# v12.net
KiCad netlist of a schematic drawn in EAGLE
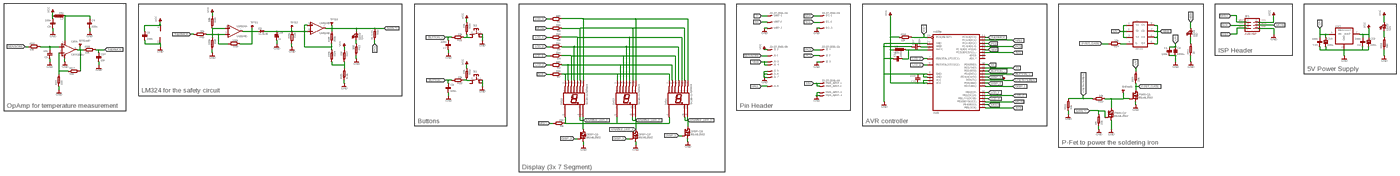
[diagram p0: schematic, sheet 1, overview]
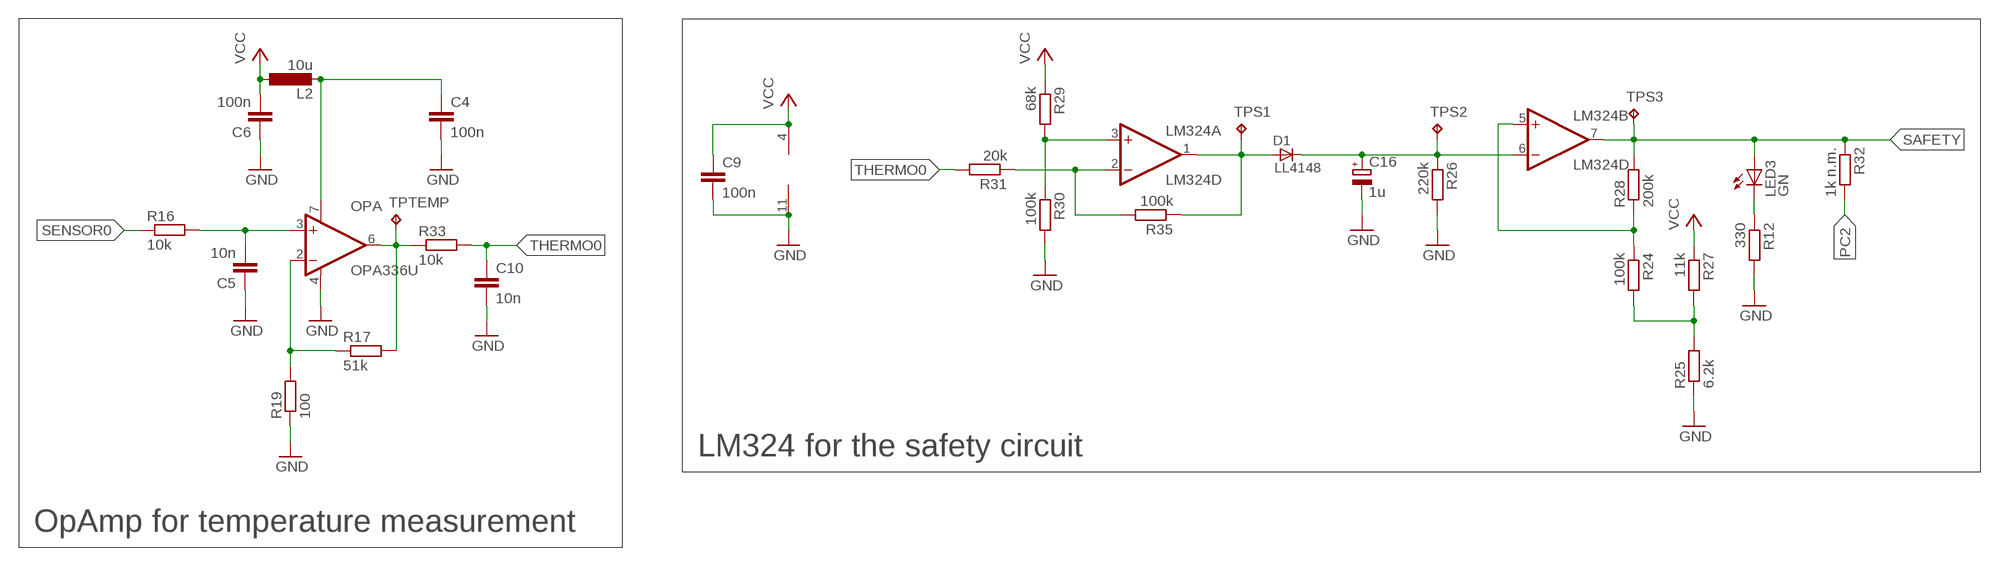
[diagram p1: schematic, sheet 1, part 1 of 4]
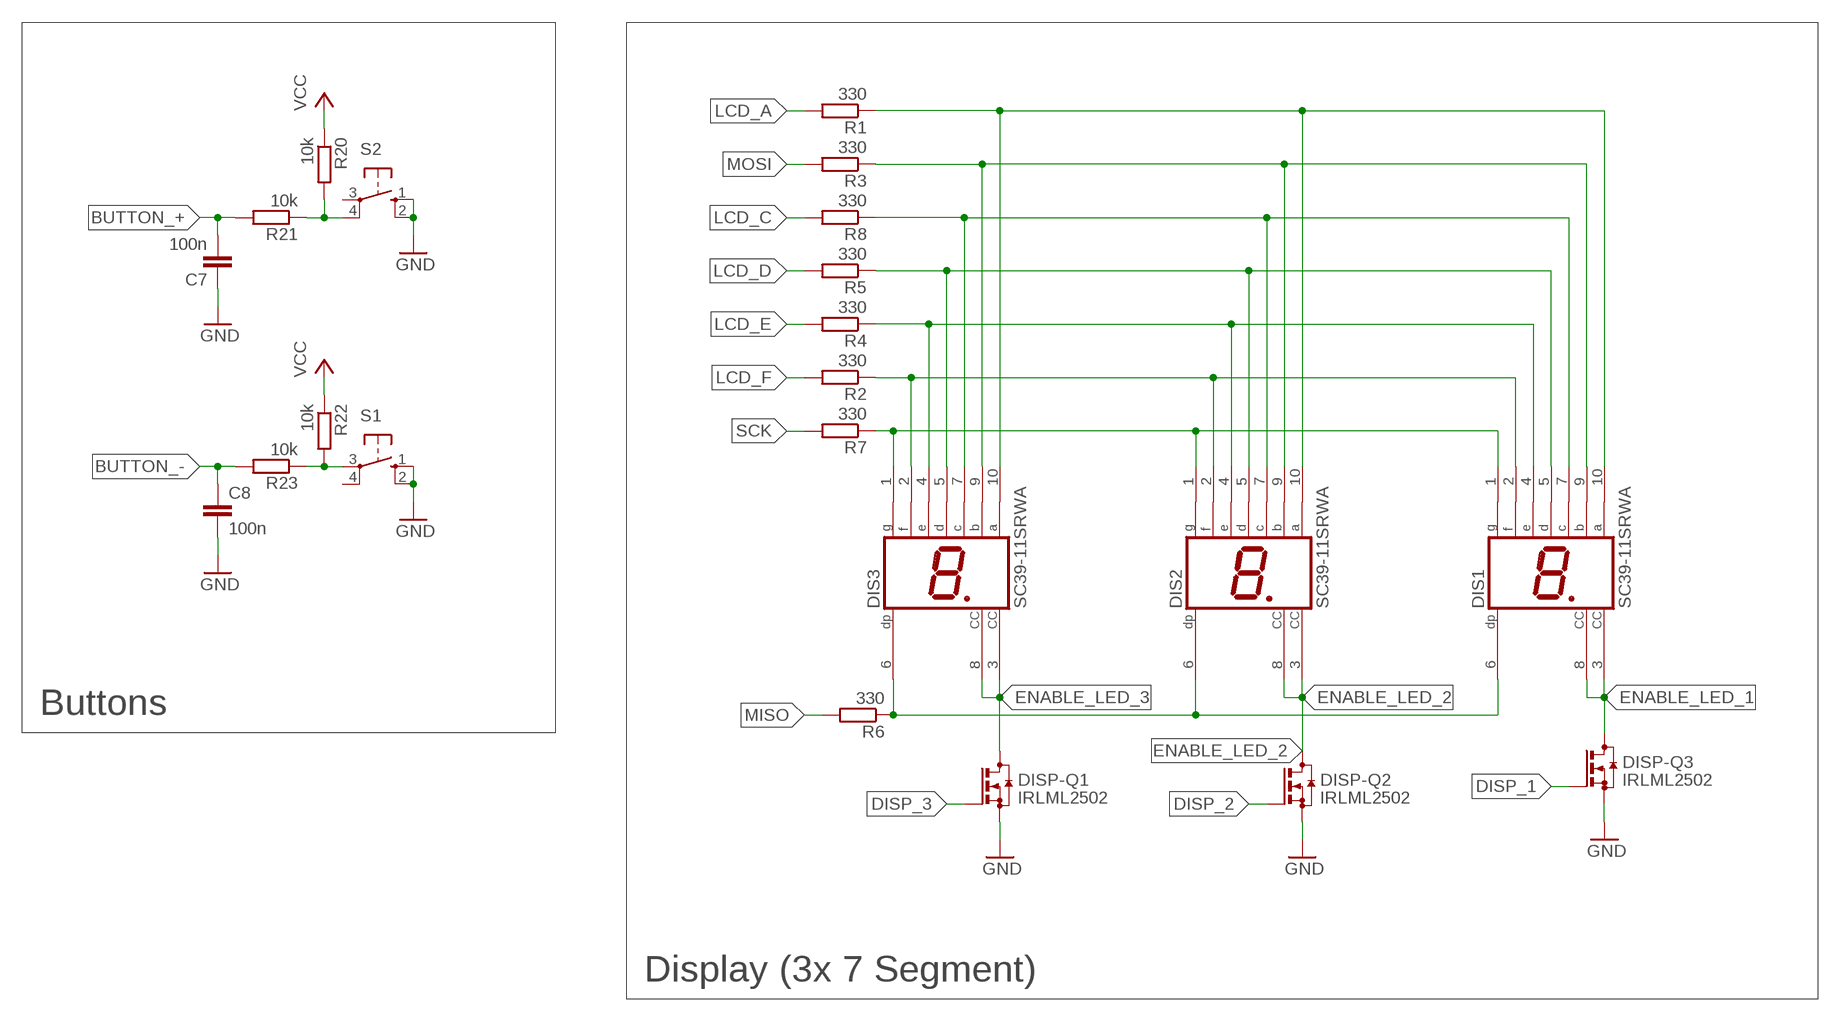
[diagram p2: schematic, sheet 1, part 2 of 4]
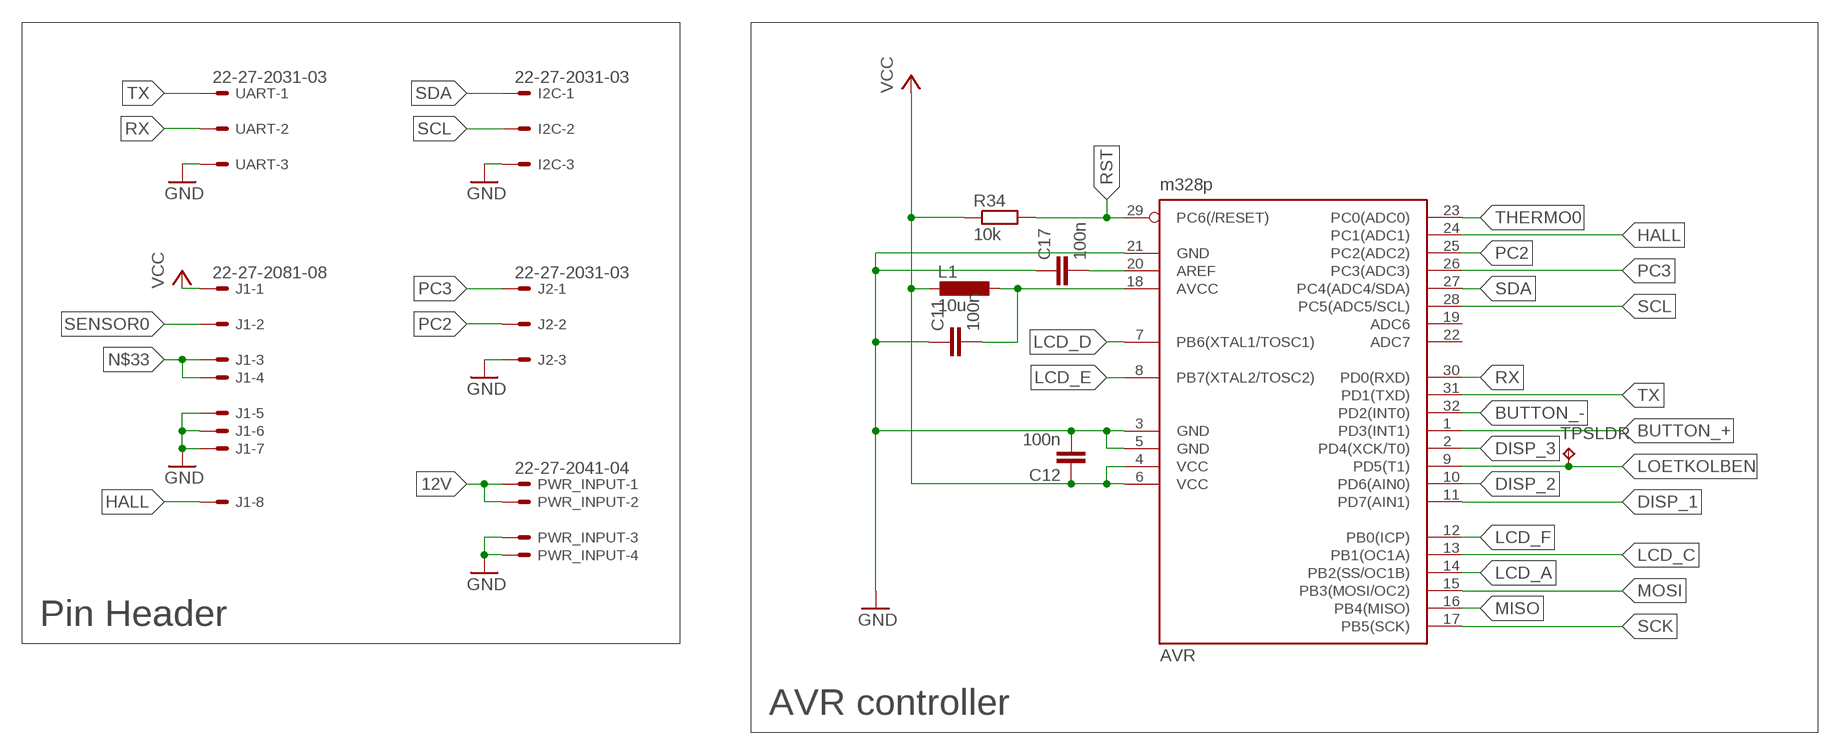
[diagram p3: schematic, sheet 1, part 3 of 4]
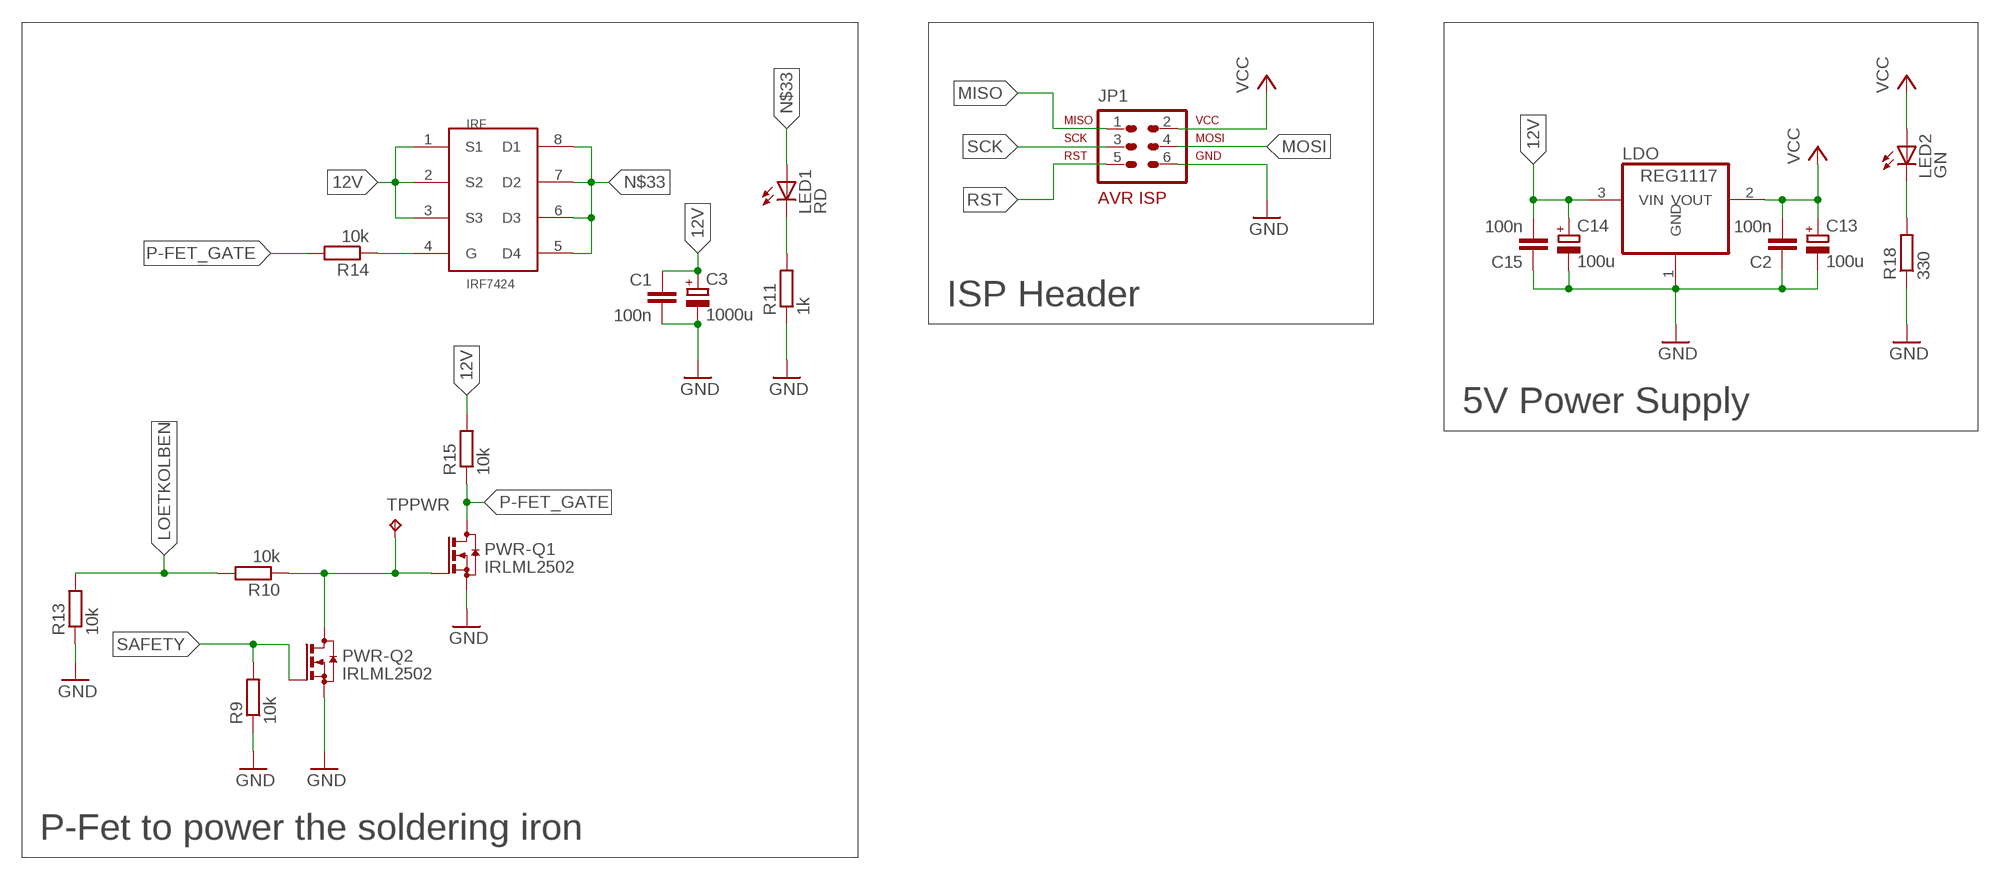
[diagram p4: schematic, sheet 1, part 4 of 4]

(export (version "E")
  (design (tool "Eeschema 10.0.6"))
  (components
    (comp (ref "AVR")
      (value "m328p")
      (footprint "eagle-import:TQFP32-08")
      (fields (field (name "MPN") "ATMEGA8-16AU"))
      (libsource (lib "eagle-import") (part "MEGA8-AI"))
    )
    (comp (ref "C1")
      (value "100n")
      (footprint "eagle-import:C0603")
      (libsource (lib "eagle-import") (part "C-EUC0603"))
    )
    (comp (ref "C2")
      (value "100n")
      (footprint "eagle-import:C0603")
      (libsource (lib "eagle-import") (part "C-EUC0603"))
    )
    (comp (ref "C3")
      (value "1000u")
      (footprint "eagle-import:E5-13")
      (libsource (lib "eagle-import") (part "CPOL-EUE5-13"))
    )
    (comp (ref "C4")
      (value "100n")
      (footprint "eagle-import:C0603")
      (libsource (lib "eagle-import") (part "C-EUC0603"))
    )
    (comp (ref "C5")
      (value "10n")
      (footprint "eagle-import:C0603")
      (libsource (lib "eagle-import") (part "C-EUC0603"))
    )
    (comp (ref "C6")
      (value "100n")
      (footprint "eagle-import:C0603")
      (libsource (lib "eagle-import") (part "C-EUC0603"))
    )
    (comp (ref "C7")
      (value "100n")
      (footprint "eagle-import:C0603")
      (libsource (lib "eagle-import") (part "C-EUC0603"))
    )
    (comp (ref "C8")
      (value "100n")
      (footprint "eagle-import:C0603")
      (libsource (lib "eagle-import") (part "C-EUC0603"))
    )
    (comp (ref "C9")
      (value "100n")
      (footprint "eagle-import:C0603")
      (libsource (lib "eagle-import") (part "C-EUC0603"))
    )
    (comp (ref "C10")
      (value "10n")
      (footprint "eagle-import:C0603")
      (libsource (lib "eagle-import") (part "C-EUC0603"))
    )
    (comp (ref "C11")
      (value "100n")
      (footprint "eagle-import:C0603")
      (libsource (lib "eagle-import") (part "C-EUC0603"))
    )
    (comp (ref "C12")
      (value "100n")
      (footprint "eagle-import:C0603")
      (libsource (lib "eagle-import") (part "C-EUC0603"))
    )
    (comp (ref "C13")
      (value "100u")
      (footprint "eagle-import:E2-5")
      (libsource (lib "eagle-import") (part "CPOL-EUE2-5"))
    )
    (comp (ref "C14")
      (value "100u")
      (footprint "eagle-import:E2-5")
      (libsource (lib "eagle-import") (part "CPOL-EUE2-5"))
    )
    (comp (ref "C15")
      (value "100n")
      (footprint "eagle-import:C0603")
      (libsource (lib "eagle-import") (part "C-EUC0603"))
    )
    (comp (ref "C16")
      (value "1u")
      (footprint "eagle-import:E2-5")
      (libsource (lib "eagle-import") (part "CPOL-EUE2-5"))
    )
    (comp (ref "C17")
      (value "100n")
      (footprint "eagle-import:C0603")
      (libsource (lib "eagle-import") (part "C-EUC0603"))
    )
    (comp (ref "D1")
      (value "LL4148")
      (footprint "eagle-import:SOD80_DO213AA_MINIMELF")
      (libsource (lib "eagle-import") (part "LL4148"))
    )
    (comp (ref "DIS1")
      (value "SC39-11SRWA")
      (footprint "eagle-import:HDSP-E")
      (libsource (lib "eagle-import") (part "SC39-11SRWA"))
    )
    (comp (ref "DIS2")
      (value "SC39-11SRWA")
      (footprint "eagle-import:HDSP-E")
      (libsource (lib "eagle-import") (part "SC39-11SRWA"))
    )
    (comp (ref "DIS3")
      (value "SC39-11SRWA")
      (footprint "eagle-import:HDSP-E")
      (libsource (lib "eagle-import") (part "SC39-11SRWA"))
    )
    (comp (ref "DISP-Q1")
      (value "IRLML2502")
      (footprint "eagle-import:SOT23")
      (libsource (lib "eagle-import") (part "BSS123"))
    )
    (comp (ref "DISP-Q2")
      (value "IRLML2502")
      (footprint "eagle-import:SOT23")
      (libsource (lib "eagle-import") (part "BSS123"))
    )
    (comp (ref "DISP-Q3")
      (value "IRLML2502")
      (footprint "eagle-import:SOT23")
      (libsource (lib "eagle-import") (part "BSS123"))
    )
    (comp (ref "I2C")
      (value "22-27-2031-03")
      (footprint "eagle-import:6410-03")
      (libsource (lib "eagle-import") (part "22-?-0327-2031"))
    )
    (comp (ref "IRF")
      (value "IRF7424")
      (footprint "eagle-import:SO-08")
      (libsource (lib "eagle-import") (part "IRF7424"))
    )
    (comp (ref "J1")
      (value "22-27-2081-08")
      (footprint "eagle-import:6410-08")
      (libsource (lib "eagle-import") (part "22-?-0827-2081"))
    )
    (comp (ref "J2")
      (value "22-27-2031-03")
      (footprint "eagle-import:6410-03")
      (libsource (lib "eagle-import") (part "22-?-0327-2031"))
    )
    (comp (ref "JP1")
      (value "AVR-ISP-6VERT")
      (footprint "eagle-import:AVR-ISP-6")
      (libsource (lib "eagle-import") (part "AVR-ISP-6VERT"))
    )
    (comp (ref "L1")
      (value "10u")
      (footprint "eagle-import:L2825P")
      (libsource (lib "eagle-import") (part "L-EUL2825P"))
    )
    (comp (ref "L2")
      (value "10u")
      (footprint "eagle-import:L2825P")
      (libsource (lib "eagle-import") (part "L-EUL2825P"))
    )
    (comp (ref "LDO")
      (value "REG1117")
      (footprint "eagle-import:SOT223")
      (libsource (lib "eagle-import") (part "REG1117"))
    )
    (comp (ref "LED1")
      (value "RD")
      (footprint "eagle-import:CHIP-LED0805")
      (libsource (lib "eagle-import") (part "LEDCHIP-LED0805"))
    )
    (comp (ref "LED2")
      (value "GN")
      (footprint "eagle-import:CHIP-LED0805")
      (libsource (lib "eagle-import") (part "LEDCHIP-LED0805"))
    )
    (comp (ref "LED3")
      (value "GN")
      (footprint "eagle-import:CHIP-LED0805")
      (libsource (lib "eagle-import") (part "LEDCHIP-LED0805"))
    )
    (comp (ref "LM324")
      (value "LM324D")
      (footprint "eagle-import:SO14")
      (libsource (lib "eagle-import") (part "LM324D"))
    )
    (comp (ref "OPA")
      (value "OPA336U")
      (footprint "eagle-import:SO08")
      (fields (field (name "MF") "TEXAS INSTRUMENT CONNECTORS") (field (name "MPN") "OPA336UA"))
      (libsource (lib "eagle-import") (part "OPA336U"))
    )
    (comp (ref "PWR-Q1")
      (value "IRLML2502")
      (footprint "eagle-import:SOT23")
      (libsource (lib "eagle-import") (part "BSS123"))
    )
    (comp (ref "PWR-Q2")
      (value "IRLML2502")
      (footprint "eagle-import:SOT23")
      (libsource (lib "eagle-import") (part "BSS123"))
    )
    (comp (ref "PWR_INPUT")
      (value "22-27-2041-04")
      (footprint "eagle-import:6410-04")
      (libsource (lib "eagle-import") (part "22-?-0427-2041"))
    )
    (comp (ref "R1")
      (value "330")
      (footprint "eagle-import:R0603")
      (libsource (lib "eagle-import") (part "R-EU_R0603"))
    )
    (comp (ref "R2")
      (value "330")
      (footprint "eagle-import:R0603")
      (libsource (lib "eagle-import") (part "R-EU_R0603"))
    )
    (comp (ref "R3")
      (value "330")
      (footprint "eagle-import:R0603")
      (libsource (lib "eagle-import") (part "R-EU_R0603"))
    )
    (comp (ref "R4")
      (value "330")
      (footprint "eagle-import:R0603")
      (libsource (lib "eagle-import") (part "R-EU_R0603"))
    )
    (comp (ref "R5")
      (value "330")
      (footprint "eagle-import:R0603")
      (libsource (lib "eagle-import") (part "R-EU_R0603"))
    )
    (comp (ref "R6")
      (value "330")
      (footprint "eagle-import:R0603")
      (libsource (lib "eagle-import") (part "R-EU_R0603"))
    )
    (comp (ref "R7")
      (value "330")
      (footprint "eagle-import:R0603")
      (libsource (lib "eagle-import") (part "R-EU_R0603"))
    )
    (comp (ref "R8")
      (value "330")
      (footprint "eagle-import:R0603")
      (libsource (lib "eagle-import") (part "R-EU_R0603"))
    )
    (comp (ref "R9")
      (value "10k")
      (footprint "eagle-import:R0603")
      (libsource (lib "eagle-import") (part "R-EU_R0603"))
    )
    (comp (ref "R10")
      (value "10k")
      (footprint "eagle-import:R0603")
      (libsource (lib "eagle-import") (part "R-EU_R0603"))
    )
    (comp (ref "R11")
      (value "1k")
      (footprint "eagle-import:R0603")
      (libsource (lib "eagle-import") (part "R-EU_R0603"))
    )
    (comp (ref "R12")
      (value "330")
      (footprint "eagle-import:R0603")
      (libsource (lib "eagle-import") (part "R-EU_R0603"))
    )
    (comp (ref "R13")
      (value "10k")
      (footprint "eagle-import:R0603")
      (libsource (lib "eagle-import") (part "R-EU_R0603"))
    )
    (comp (ref "R14")
      (value "10k")
      (footprint "eagle-import:R0603")
      (libsource (lib "eagle-import") (part "R-EU_R0603"))
    )
    (comp (ref "R15")
      (value "10k")
      (footprint "eagle-import:R0603")
      (libsource (lib "eagle-import") (part "R-EU_R0603"))
    )
    (comp (ref "R16")
      (value "10k")
      (footprint "eagle-import:R0603")
      (libsource (lib "eagle-import") (part "R-EU_R0603"))
    )
    (comp (ref "R17")
      (value "51k")
      (footprint "eagle-import:R0603")
      (libsource (lib "eagle-import") (part "R-EU_R0603"))
    )
    (comp (ref "R18")
      (value "330")
      (footprint "eagle-import:R0603")
      (libsource (lib "eagle-import") (part "R-EU_R0603"))
    )
    (comp (ref "R19")
      (value "100")
      (footprint "eagle-import:R0603")
      (libsource (lib "eagle-import") (part "R-EU_R0603"))
    )
    (comp (ref "R20")
      (value "10k")
      (footprint "eagle-import:R0603")
      (libsource (lib "eagle-import") (part "R-EU_R0603"))
    )
    (comp (ref "R21")
      (value "10k")
      (footprint "eagle-import:R0603")
      (libsource (lib "eagle-import") (part "R-EU_R0603"))
    )
    (comp (ref "R22")
      (value "10k")
      (footprint "eagle-import:R0603")
      (libsource (lib "eagle-import") (part "R-EU_R0603"))
    )
    (comp (ref "R23")
      (value "10k")
      (footprint "eagle-import:R0603")
      (libsource (lib "eagle-import") (part "R-EU_R0603"))
    )
    (comp (ref "R24")
      (value "100k")
      (footprint "eagle-import:R0603")
      (libsource (lib "eagle-import") (part "R-EU_R0603"))
    )
    (comp (ref "R25")
      (value "6.2k")
      (footprint "eagle-import:R0603")
      (libsource (lib "eagle-import") (part "R-EU_R0603"))
    )
    (comp (ref "R26")
      (value "220k")
      (footprint "eagle-import:R0603")
      (libsource (lib "eagle-import") (part "R-EU_R0603"))
    )
    (comp (ref "R27")
      (value "11k")
      (footprint "eagle-import:R0603")
      (libsource (lib "eagle-import") (part "R-EU_R0603"))
    )
    (comp (ref "R28")
      (value "200k")
      (footprint "eagle-import:R0603")
      (libsource (lib "eagle-import") (part "R-EU_R0603"))
    )
    (comp (ref "R29")
      (value "68k")
      (footprint "eagle-import:R0603")
      (libsource (lib "eagle-import") (part "R-EU_R0603"))
    )
    (comp (ref "R30")
      (value "100k")
      (footprint "eagle-import:R0603")
      (libsource (lib "eagle-import") (part "R-EU_R0603"))
    )
    (comp (ref "R31")
      (value "20k")
      (footprint "eagle-import:R0603")
      (libsource (lib "eagle-import") (part "R-EU_R0603"))
    )
    (comp (ref "R32")
      (value "1k n.m.")
      (footprint "eagle-import:R0603")
      (libsource (lib "eagle-import") (part "R-EU_R0603"))
    )
    (comp (ref "R33")
      (value "10k")
      (footprint "eagle-import:R0603")
      (libsource (lib "eagle-import") (part "R-EU_R0603"))
    )
    (comp (ref "R34")
      (value "10k")
      (footprint "eagle-import:R0603")
      (libsource (lib "eagle-import") (part "R-EU_R0603"))
    )
    (comp (ref "R35")
      (value "100k")
      (footprint "eagle-import:R0603")
      (libsource (lib "eagle-import") (part "R-EU_R0603"))
    )
    (comp (ref "S1")
      (value "10-XX")
      (footprint "eagle-import:B3F-10XX")
      (fields (field (name "MPN") "B3F-1000"))
      (libsource (lib "eagle-import") (part "10-XX"))
    )
    (comp (ref "S2")
      (value "10-XX")
      (footprint "eagle-import:B3F-10XX")
      (fields (field (name "MPN") "B3F-1000"))
      (libsource (lib "eagle-import") (part "10-XX"))
    )
    (comp (ref "TPPWR")
      (value "TPB1,27")
      (footprint "eagle-import:B1,27")
      (libsource (lib "eagle-import") (part "TPB1,27"))
    )
    (comp (ref "TPS1")
      (value "TPB1,27")
      (footprint "eagle-import:B1,27")
      (libsource (lib "eagle-import") (part "TPB1,27"))
    )
    (comp (ref "TPS2")
      (value "TPB1,27")
      (footprint "eagle-import:B1,27")
      (libsource (lib "eagle-import") (part "TPB1,27"))
    )
    (comp (ref "TPS3")
      (value "TPB1,27")
      (footprint "eagle-import:B1,27")
      (libsource (lib "eagle-import") (part "TPB1,27"))
    )
    (comp (ref "TPSLDR")
      (value "TPB1,27")
      (footprint "eagle-import:B1,27")
      (libsource (lib "eagle-import") (part "TPB1,27"))
    )
    (comp (ref "TPTEMP")
      (value "TPB1,27")
      (footprint "eagle-import:B1,27")
      (libsource (lib "eagle-import") (part "TPB1,27"))
    )
    (comp (ref "UART")
      (value "22-27-2031-03")
      (footprint "eagle-import:6410-03")
      (libsource (lib "eagle-import") (part "22-?-0327-2031"))
    )
  )
  (nets
    (net (code "1") (name "12V") (class "Default")
      (node (ref "C1") (pin "1") (pinfunction "1_1") (pintype "passive"))
      (node (ref "C14") (pin "+") (pinfunction "+_+") (pintype "passive"))
      (node (ref "C15") (pin "2") (pinfunction "2_2") (pintype "passive"))
      (node (ref "C3") (pin "+") (pinfunction "+_+") (pintype "passive"))
      (node (ref "IRF") (pin "1") (pinfunction "S1_1") (pintype "bidirectional"))
      (node (ref "IRF") (pin "2") (pinfunction "S2_2") (pintype "bidirectional"))
      (node (ref "IRF") (pin "3") (pinfunction "S3_3") (pintype "bidirectional"))
      (node (ref "LDO") (pin "3") (pinfunction "VIN_3") (pintype "input"))
      (node (ref "PWR_INPUT") (pin "1") (pinfunction "S_1") (pintype "passive"))
      (node (ref "PWR_INPUT") (pin "2") (pinfunction "S_2") (pintype "passive"))
      (node (ref "R15") (pin "2") (pinfunction "2_2") (pintype "passive"))
    )
    (net (code "2") (name "BUTTON_+") (class "Default")
      (node (ref "AVR") (pin "1") (pinfunction "PD3(INT1)_1") (pintype "bidirectional"))
      (node (ref "C7") (pin "2") (pinfunction "2_2") (pintype "passive"))
      (node (ref "R21") (pin "2") (pinfunction "2_2") (pintype "passive"))
    )
    (net (code "3") (name "BUTTON_-") (class "Default")
      (node (ref "AVR") (pin "32") (pinfunction "PD2(INT0)_32") (pintype "bidirectional"))
      (node (ref "C8") (pin "1") (pinfunction "1_1") (pintype "passive"))
      (node (ref "R23") (pin "2") (pinfunction "2_2") (pintype "passive"))
    )
    (net (code "4") (name "DISP_1") (class "Default")
      (node (ref "AVR") (pin "11") (pinfunction "PD7(AIN1)_11") (pintype "bidirectional"))
      (node (ref "DISP-Q3") (pin "1") (pinfunction "G_1") (pintype "passive"))
    )
    (net (code "5") (name "DISP_2") (class "Default")
      (node (ref "AVR") (pin "10") (pinfunction "PD6(AIN0)_10") (pintype "bidirectional"))
      (node (ref "DISP-Q2") (pin "1") (pinfunction "G_1") (pintype "passive"))
    )
    (net (code "6") (name "DISP_3") (class "Default")
      (node (ref "AVR") (pin "2") (pinfunction "PD4(XCK/T0)_2") (pintype "bidirectional"))
      (node (ref "DISP-Q1") (pin "1") (pinfunction "G_1") (pintype "passive"))
    )
    (net (code "7") (name "ENABLE_LED_1") (class "Default")
      (node (ref "DIS1") (pin "3") (pinfunction "CC_3") (pintype "passive"))
      (node (ref "DIS1") (pin "8") (pinfunction "CC_8") (pintype "passive"))
      (node (ref "DISP-Q3") (pin "3") (pinfunction "D_3") (pintype "passive"))
    )
    (net (code "8") (name "ENABLE_LED_2") (class "Default")
      (node (ref "DIS2") (pin "3") (pinfunction "CC_3") (pintype "passive"))
      (node (ref "DIS2") (pin "8") (pinfunction "CC_8") (pintype "passive"))
      (node (ref "DISP-Q2") (pin "3") (pinfunction "D_3") (pintype "passive"))
    )
    (net (code "9") (name "ENABLE_LED_3") (class "Default")
      (node (ref "DIS3") (pin "3") (pinfunction "CC_3") (pintype "passive"))
      (node (ref "DIS3") (pin "8") (pinfunction "CC_8") (pintype "passive"))
      (node (ref "DISP-Q1") (pin "3") (pinfunction "D_3") (pintype "passive"))
    )
    (net (code "10") (name "GND") (class "Default")
      (node (ref "AVR") (pin "21") (pinfunction "GND_21") (pintype "power_in"))
      (node (ref "AVR") (pin "3") (pinfunction "GND_3") (pintype "power_in"))
      (node (ref "AVR") (pin "5") (pinfunction "GND_5") (pintype "power_in"))
      (node (ref "C1") (pin "2") (pinfunction "2_2") (pintype "passive"))
      (node (ref "C10") (pin "2") (pinfunction "2_2") (pintype "passive"))
      (node (ref "C11") (pin "1") (pinfunction "1_1") (pintype "passive"))
      (node (ref "C12") (pin "2") (pinfunction "2_2") (pintype "passive"))
      (node (ref "C13") (pin "-") (pinfunction "-_-") (pintype "passive"))
      (node (ref "C14") (pin "-") (pinfunction "-_-") (pintype "passive"))
      (node (ref "C15") (pin "1") (pinfunction "1_1") (pintype "passive"))
      (node (ref "C16") (pin "-") (pinfunction "-_-") (pintype "passive"))
      (node (ref "C17") (pin "1") (pinfunction "1_1") (pintype "passive"))
      (node (ref "C2") (pin "1") (pinfunction "1_1") (pintype "passive"))
      (node (ref "C3") (pin "-") (pinfunction "-_-") (pintype "passive"))
      (node (ref "C4") (pin "2") (pinfunction "2_2") (pintype "passive"))
      (node (ref "C5") (pin "1") (pinfunction "1_1") (pintype "passive"))
      (node (ref "C6") (pin "1") (pinfunction "1_1") (pintype "passive"))
      (node (ref "C7") (pin "1") (pinfunction "1_1") (pintype "passive"))
      (node (ref "C8") (pin "2") (pinfunction "2_2") (pintype "passive"))
      (node (ref "C9") (pin "2") (pinfunction "2_2") (pintype "passive"))
      (node (ref "DISP-Q1") (pin "2") (pinfunction "S_2") (pintype "passive"))
      (node (ref "DISP-Q2") (pin "2") (pinfunction "S_2") (pintype "passive"))
      (node (ref "DISP-Q3") (pin "2") (pinfunction "S_2") (pintype "passive"))
      (node (ref "I2C") (pin "3") (pinfunction "S_3") (pintype "passive"))
      (node (ref "J1") (pin "5") (pinfunction "S_5") (pintype "passive"))
      (node (ref "J1") (pin "6") (pinfunction "S_6") (pintype "passive"))
      (node (ref "J1") (pin "7") (pinfunction "S_7") (pintype "passive"))
      (node (ref "J2") (pin "3") (pinfunction "S_3") (pintype "passive"))
      (node (ref "JP1") (pin "6") (pinfunction "6_6") (pintype "passive"))
      (node (ref "LDO") (pin "1") (pinfunction "GND_1") (pintype "power_in"))
      (node (ref "LM324") (pin "11") (pinfunction "V-_11") (pintype "power_in"))
      (node (ref "OPA") (pin "4") (pinfunction "V-_4") (pintype "power_in"))
      (node (ref "PWR-Q1") (pin "2") (pinfunction "S_2") (pintype "passive"))
      (node (ref "PWR-Q2") (pin "2") (pinfunction "S_2") (pintype "passive"))
      (node (ref "PWR_INPUT") (pin "3") (pinfunction "S_3") (pintype "passive"))
      (node (ref "PWR_INPUT") (pin "4") (pinfunction "S_4") (pintype "passive"))
      (node (ref "R11") (pin "1") (pinfunction "1_1") (pintype "passive"))
      (node (ref "R12") (pin "2") (pinfunction "2_2") (pintype "passive"))
      (node (ref "R13") (pin "1") (pinfunction "1_1") (pintype "passive"))
      (node (ref "R18") (pin "1") (pinfunction "1_1") (pintype "passive"))
      (node (ref "R19") (pin "1") (pinfunction "1_1") (pintype "passive"))
      (node (ref "R25") (pin "1") (pinfunction "1_1") (pintype "passive"))
      (node (ref "R26") (pin "2") (pinfunction "2_2") (pintype "passive"))
      (node (ref "R30") (pin "2") (pinfunction "2_2") (pintype "passive"))
      (node (ref "R9") (pin "1") (pinfunction "1_1") (pintype "passive"))
      (node (ref "S1") (pin "1") (pinfunction "S_1") (pintype "passive"))
      (node (ref "S1") (pin "2") (pinfunction "S1_2") (pintype "passive"))
      (node (ref "S2") (pin "1") (pinfunction "S_1") (pintype "passive"))
      (node (ref "S2") (pin "2") (pinfunction "S1_2") (pintype "passive"))
      (node (ref "UART") (pin "3") (pinfunction "S_3") (pintype "passive"))
    )
    (net (code "11") (name "HALL") (class "Default")
      (node (ref "AVR") (pin "24") (pinfunction "PC1(ADC1)_24") (pintype "bidirectional"))
      (node (ref "J1") (pin "8") (pinfunction "S_8") (pintype "passive"))
    )
    (net (code "12") (name "LCD_A") (class "Default")
      (node (ref "AVR") (pin "14") (pinfunction "PB2(SS/OC1B)_14") (pintype "bidirectional"))
      (node (ref "R1") (pin "2") (pinfunction "2_2") (pintype "passive"))
    )
    (net (code "13") (name "LCD_C") (class "Default")
      (node (ref "AVR") (pin "13") (pinfunction "PB1(OC1A)_13") (pintype "bidirectional"))
      (node (ref "R8") (pin "2") (pinfunction "2_2") (pintype "passive"))
    )
    (net (code "14") (name "LCD_D") (class "Default")
      (node (ref "AVR") (pin "7") (pinfunction "PB6(XTAL1/TOSC1)_7") (pintype "bidirectional"))
      (node (ref "R5") (pin "2") (pinfunction "2_2") (pintype "passive"))
    )
    (net (code "15") (name "LCD_E") (class "Default")
      (node (ref "AVR") (pin "8") (pinfunction "PB7(XTAL2/TOSC2)_8") (pintype "bidirectional"))
      (node (ref "R4") (pin "2") (pinfunction "2_2") (pintype "passive"))
    )
    (net (code "16") (name "LCD_F") (class "Default")
      (node (ref "AVR") (pin "12") (pinfunction "PB0(ICP)_12") (pintype "bidirectional"))
      (node (ref "R2") (pin "2") (pinfunction "2_2") (pintype "passive"))
    )
    (net (code "17") (name "LOETKOLBEN") (class "Default")
      (node (ref "AVR") (pin "9") (pinfunction "PD5(T1)_9") (pintype "bidirectional"))
      (node (ref "R10") (pin "2") (pinfunction "2_2") (pintype "passive"))
      (node (ref "R13") (pin "2") (pinfunction "2_2") (pintype "passive"))
      (node (ref "TPSLDR") (pin "TP") (pinfunction "TP_TP") (pintype "input"))
    )
    (net (code "18") (name "MISO") (class "Default")
      (node (ref "AVR") (pin "16") (pinfunction "PB4(MISO)_16") (pintype "bidirectional"))
      (node (ref "JP1") (pin "1") (pinfunction "1_1") (pintype "passive"))
      (node (ref "R6") (pin "2") (pinfunction "2_2") (pintype "passive"))
    )
    (net (code "19") (name "MOSI") (class "Default")
      (node (ref "AVR") (pin "15") (pinfunction "PB3(MOSI/OC2)_15") (pintype "bidirectional"))
      (node (ref "JP1") (pin "4") (pinfunction "4_4") (pintype "passive"))
      (node (ref "R3") (pin "2") (pinfunction "2_2") (pintype "passive"))
    )
    (net (code "20") (name "N$33") (class "Default")
      (node (ref "IRF") (pin "5") (pinfunction "D4_5") (pintype "bidirectional"))
      (node (ref "IRF") (pin "6") (pinfunction "D3_6") (pintype "bidirectional"))
      (node (ref "IRF") (pin "7") (pinfunction "D2_7") (pintype "bidirectional"))
      (node (ref "IRF") (pin "8") (pinfunction "D1_8") (pintype "bidirectional"))
      (node (ref "J1") (pin "3") (pinfunction "S_3") (pintype "passive"))
      (node (ref "J1") (pin "4") (pinfunction "S_4") (pintype "passive"))
      (node (ref "LED1") (pin "A") (pinfunction "A_A") (pintype "passive"))
    )
    (net (code "21") (name "Net-(AVR-AREF)") (class "Default")
      (node (ref "AVR") (pin "20") (pinfunction "AREF_20") (pintype "passive"))
      (node (ref "C17") (pin "2") (pinfunction "2_2") (pintype "passive"))
    )
    (net (code "22") (name "Net-(AVR-AVCC)") (class "Default")
      (node (ref "AVR") (pin "18") (pinfunction "AVCC_18") (pintype "power_in"))
      (node (ref "C11") (pin "2") (pinfunction "2_2") (pintype "passive"))
      (node (ref "L1") (pin "1") (pinfunction "1_1") (pintype "passive"))
    )
    (net (code "23") (name "Net-(DIS1-A)") (class "Default")
      (node (ref "DIS1") (pin "10") (pinfunction "A_10") (pintype "passive"))
      (node (ref "DIS2") (pin "10") (pinfunction "A_10") (pintype "passive"))
      (node (ref "DIS3") (pin "10") (pinfunction "A_10") (pintype "passive"))
      (node (ref "R1") (pin "1") (pinfunction "1_1") (pintype "passive"))
    )
    (net (code "24") (name "Net-(DIS1-B)") (class "Default")
      (node (ref "DIS1") (pin "9") (pinfunction "B_9") (pintype "passive"))
      (node (ref "DIS2") (pin "9") (pinfunction "B_9") (pintype "passive"))
      (node (ref "DIS3") (pin "9") (pinfunction "B_9") (pintype "passive"))
      (node (ref "R3") (pin "1") (pinfunction "1_1") (pintype "passive"))
    )
    (net (code "25") (name "Net-(DIS1-C)") (class "Default")
      (node (ref "DIS1") (pin "7") (pinfunction "C_7") (pintype "passive"))
      (node (ref "DIS2") (pin "7") (pinfunction "C_7") (pintype "passive"))
      (node (ref "DIS3") (pin "7") (pinfunction "C_7") (pintype "passive"))
      (node (ref "R8") (pin "1") (pinfunction "1_1") (pintype "passive"))
    )
    (net (code "26") (name "Net-(DIS1-D)") (class "Default")
      (node (ref "DIS1") (pin "5") (pinfunction "D_5") (pintype "passive"))
      (node (ref "DIS2") (pin "5") (pinfunction "D_5") (pintype "passive"))
      (node (ref "DIS3") (pin "5") (pinfunction "D_5") (pintype "passive"))
      (node (ref "R5") (pin "1") (pinfunction "1_1") (pintype "passive"))
    )
    (net (code "27") (name "Net-(DIS1-DP)") (class "Default")
      (node (ref "DIS1") (pin "6") (pinfunction "DP_6") (pintype "passive"))
      (node (ref "DIS2") (pin "6") (pinfunction "DP_6") (pintype "passive"))
      (node (ref "DIS3") (pin "6") (pinfunction "DP_6") (pintype "passive"))
      (node (ref "R6") (pin "1") (pinfunction "1_1") (pintype "passive"))
    )
    (net (code "28") (name "Net-(DIS1-E)") (class "Default")
      (node (ref "DIS1") (pin "4") (pinfunction "E_4") (pintype "passive"))
      (node (ref "DIS2") (pin "4") (pinfunction "E_4") (pintype "passive"))
      (node (ref "DIS3") (pin "4") (pinfunction "E_4") (pintype "passive"))
      (node (ref "R4") (pin "1") (pinfunction "1_1") (pintype "passive"))
    )
    (net (code "29") (name "Net-(DIS1-F)") (class "Default")
      (node (ref "DIS1") (pin "2") (pinfunction "F_2") (pintype "passive"))
      (node (ref "DIS2") (pin "2") (pinfunction "F_2") (pintype "passive"))
      (node (ref "DIS3") (pin "2") (pinfunction "F_2") (pintype "passive"))
      (node (ref "R2") (pin "1") (pinfunction "1_1") (pintype "passive"))
    )
    (net (code "30") (name "Net-(DIS1-G)") (class "Default")
      (node (ref "DIS1") (pin "1") (pinfunction "G_1") (pintype "passive"))
      (node (ref "DIS2") (pin "1") (pinfunction "G_1") (pintype "passive"))
      (node (ref "DIS3") (pin "1") (pinfunction "G_1") (pintype "passive"))
      (node (ref "R7") (pin "1") (pinfunction "1_1") (pintype "passive"))
    )
    (net (code "31") (name "Net-(IRF-G)") (class "Default")
      (node (ref "IRF") (pin "4") (pinfunction "G_4") (pintype "bidirectional"))
      (node (ref "R14") (pin "1") (pinfunction "1_1") (pintype "passive"))
    )
    (net (code "32") (name "Net-(LED1-PadC)") (class "Default")
      (node (ref "LED1") (pin "C") (pinfunction "C_C") (pintype "passive"))
      (node (ref "R11") (pin "2") (pinfunction "2_2") (pintype "passive"))
    )
    (net (code "33") (name "Net-(LED2-PadC)") (class "Default")
      (node (ref "LED2") (pin "C") (pinfunction "C_C") (pintype "passive"))
      (node (ref "R18") (pin "2") (pinfunction "2_2") (pintype "passive"))
    )
    (net (code "34") (name "Net-(LED3-PadC)") (class "Default")
      (node (ref "LED3") (pin "C") (pinfunction "C_C") (pintype "passive"))
      (node (ref "R12") (pin "1") (pinfunction "1_1") (pintype "passive"))
    )
    (net (code "35") (name "Net-(LM324A-+IN)") (class "Default")
      (node (ref "LM324") (pin "3") (pinfunction "+IN_3") (pintype "input"))
      (node (ref "R29") (pin "2") (pinfunction "2_2") (pintype "passive"))
      (node (ref "R30") (pin "1") (pinfunction "1_1") (pintype "passive"))
    )
    (net (code "36") (name "Net-(LM324A--IN)") (class "Default")
      (node (ref "LM324") (pin "2") (pinfunction "-IN_2") (pintype "input"))
      (node (ref "R31") (pin "1") (pinfunction "1_1") (pintype "passive"))
      (node (ref "R35") (pin "2") (pinfunction "2_2") (pintype "passive"))
    )
    (net (code "37") (name "Net-(LM324A-OUT)") (class "Default")
      (node (ref "D1") (pin "A") (pinfunction "A_A") (pintype "passive"))
      (node (ref "LM324") (pin "1") (pinfunction "OUT_1") (pintype "output"))
      (node (ref "R35") (pin "1") (pinfunction "1_1") (pintype "passive"))
      (node (ref "TPS1") (pin "TP") (pinfunction "TP_TP") (pintype "input"))
    )
    (net (code "38") (name "Net-(LM324B-+IN)") (class "Default")
      (node (ref "LM324") (pin "5") (pinfunction "+IN_5") (pintype "input"))
      (node (ref "R24") (pin "1") (pinfunction "1_1") (pintype "passive"))
      (node (ref "R28") (pin "1") (pinfunction "1_1") (pintype "passive"))
    )
    (net (code "39") (name "Net-(LM324B--IN)") (class "Default")
      (node (ref "C16") (pin "+") (pinfunction "+_+") (pintype "passive"))
      (node (ref "D1") (pin "C") (pinfunction "C_C") (pintype "passive"))
      (node (ref "LM324") (pin "6") (pinfunction "-IN_6") (pintype "input"))
      (node (ref "R26") (pin "1") (pinfunction "1_1") (pintype "passive"))
      (node (ref "TPS2") (pin "TP") (pinfunction "TP_TP") (pintype "input"))
    )
    (net (code "40") (name "Net-(OPA-+IN)") (class "Default")
      (node (ref "C5") (pin "2") (pinfunction "2_2") (pintype "passive"))
      (node (ref "OPA") (pin "3") (pinfunction "+IN_3") (pintype "input"))
      (node (ref "R16") (pin "2") (pinfunction "2_2") (pintype "passive"))
    )
    (net (code "41") (name "Net-(OPA--IN)") (class "Default")
      (node (ref "OPA") (pin "2") (pinfunction "-IN_2") (pintype "input"))
      (node (ref "R17") (pin "1") (pinfunction "1_1") (pintype "passive"))
      (node (ref "R19") (pin "2") (pinfunction "2_2") (pintype "passive"))
    )
    (net (code "42") (name "Net-(OPA-OUT)") (class "Default")
      (node (ref "OPA") (pin "6") (pinfunction "OUT_6") (pintype "output"))
      (node (ref "R17") (pin "2") (pinfunction "2_2") (pintype "passive"))
      (node (ref "R33") (pin "1") (pinfunction "1_1") (pintype "passive"))
      (node (ref "TPTEMP") (pin "TP") (pinfunction "TP_TP") (pintype "input"))
    )
    (net (code "43") (name "Net-(OPA-V+)") (class "Default")
      (node (ref "C4") (pin "1") (pinfunction "1_1") (pintype "passive"))
      (node (ref "L2") (pin "2") (pinfunction "2_2") (pintype "passive"))
      (node (ref "OPA") (pin "7") (pinfunction "V+_7") (pintype "power_in"))
    )
    (net (code "44") (name "Net-(PWR-Q1-G)") (class "Default")
      (node (ref "PWR-Q1") (pin "1") (pinfunction "G_1") (pintype "passive"))
      (node (ref "PWR-Q2") (pin "3") (pinfunction "D_3") (pintype "passive"))
      (node (ref "R10") (pin "1") (pinfunction "1_1") (pintype "passive"))
      (node (ref "TPPWR") (pin "TP") (pinfunction "TP_TP") (pintype "input"))
    )
    (net (code "45") (name "Net-(R24-Pad2)") (class "Default")
      (node (ref "R24") (pin "2") (pinfunction "2_2") (pintype "passive"))
      (node (ref "R25") (pin "2") (pinfunction "2_2") (pintype "passive"))
      (node (ref "R27") (pin "2") (pinfunction "2_2") (pintype "passive"))
    )
    (net (code "46") (name "Net-(S1-P)") (class "Default")
      (node (ref "R22") (pin "2") (pinfunction "2_2") (pintype "passive"))
      (node (ref "R23") (pin "1") (pinfunction "1_1") (pintype "passive"))
      (node (ref "S1") (pin "3") (pinfunction "P_3") (pintype "passive"))
    )
    (net (code "47") (name "Net-(S2-P1)") (class "Default")
      (node (ref "R20") (pin "2") (pinfunction "2_2") (pintype "passive"))
      (node (ref "R21") (pin "1") (pinfunction "1_1") (pintype "passive"))
      (node (ref "S2") (pin "4") (pinfunction "P1_4") (pintype "passive"))
    )
    (net (code "48") (name "P-FET_GATE") (class "Default")
      (node (ref "PWR-Q1") (pin "3") (pinfunction "D_3") (pintype "passive"))
      (node (ref "R14") (pin "2") (pinfunction "2_2") (pintype "passive"))
      (node (ref "R15") (pin "1") (pinfunction "1_1") (pintype "passive"))
    )
    (net (code "49") (name "PC2") (class "Default")
      (node (ref "AVR") (pin "25") (pinfunction "PC2(ADC2)_25") (pintype "bidirectional"))
      (node (ref "J2") (pin "2") (pinfunction "S_2") (pintype "passive"))
      (node (ref "R32") (pin "2") (pinfunction "2_2") (pintype "passive"))
    )
    (net (code "50") (name "PC3") (class "Default")
      (node (ref "AVR") (pin "26") (pinfunction "PC3(ADC3)_26") (pintype "bidirectional"))
      (node (ref "J2") (pin "1") (pinfunction "S_1") (pintype "passive"))
    )
    (net (code "51") (name "RST") (class "Default")
      (node (ref "AVR") (pin "29") (pinfunction "PC6(/RESET)_29") (pintype "bidirectional"))
      (node (ref "JP1") (pin "5") (pinfunction "5_5") (pintype "passive"))
      (node (ref "R34") (pin "2") (pinfunction "2_2") (pintype "passive"))
    )
    (net (code "52") (name "RX") (class "Default")
      (node (ref "AVR") (pin "30") (pinfunction "PD0(RXD)_30") (pintype "bidirectional"))
      (node (ref "UART") (pin "2") (pinfunction "S_2") (pintype "passive"))
    )
    (net (code "53") (name "SAFETY") (class "Default")
      (node (ref "LED3") (pin "A") (pinfunction "A_A") (pintype "passive"))
      (node (ref "LM324") (pin "7") (pinfunction "OUT_7") (pintype "output"))
      (node (ref "PWR-Q2") (pin "1") (pinfunction "G_1") (pintype "passive"))
      (node (ref "R28") (pin "2") (pinfunction "2_2") (pintype "passive"))
      (node (ref "R32") (pin "1") (pinfunction "1_1") (pintype "passive"))
      (node (ref "R9") (pin "2") (pinfunction "2_2") (pintype "passive"))
      (node (ref "TPS3") (pin "TP") (pinfunction "TP_TP") (pintype "input"))
    )
    (net (code "54") (name "SCK") (class "Default")
      (node (ref "AVR") (pin "17") (pinfunction "PB5(SCK)_17") (pintype "bidirectional"))
      (node (ref "JP1") (pin "3") (pinfunction "3_3") (pintype "passive"))
      (node (ref "R7") (pin "2") (pinfunction "2_2") (pintype "passive"))
    )
    (net (code "55") (name "SCL") (class "Default")
      (node (ref "AVR") (pin "28") (pinfunction "PC5(ADC5/SCL)_28") (pintype "bidirectional"))
      (node (ref "I2C") (pin "2") (pinfunction "S_2") (pintype "passive"))
    )
    (net (code "56") (name "SDA") (class "Default")
      (node (ref "AVR") (pin "27") (pinfunction "PC4(ADC4/SDA)_27") (pintype "bidirectional"))
      (node (ref "I2C") (pin "1") (pinfunction "S_1") (pintype "passive"))
    )
    (net (code "57") (name "SENSOR0") (class "Default")
      (node (ref "J1") (pin "2") (pinfunction "S_2") (pintype "passive"))
      (node (ref "R16") (pin "1") (pinfunction "1_1") (pintype "passive"))
    )
    (net (code "58") (name "THERMO0") (class "Default")
      (node (ref "AVR") (pin "23") (pinfunction "PC0(ADC0)_23") (pintype "bidirectional"))
      (node (ref "C10") (pin "1") (pinfunction "1_1") (pintype "passive"))
      (node (ref "R31") (pin "2") (pinfunction "2_2") (pintype "passive"))
      (node (ref "R33") (pin "2") (pinfunction "2_2") (pintype "passive"))
    )
    (net (code "59") (name "TX") (class "Default")
      (node (ref "AVR") (pin "31") (pinfunction "PD1(TXD)_31") (pintype "bidirectional"))
      (node (ref "UART") (pin "1") (pinfunction "S_1") (pintype "passive"))
    )
    (net (code "60") (name "VCC") (class "Default")
      (node (ref "AVR") (pin "4") (pinfunction "VCC_4") (pintype "power_in"))
      (node (ref "AVR") (pin "6") (pinfunction "VCC_6") (pintype "power_in"))
      (node (ref "C12") (pin "1") (pinfunction "1_1") (pintype "passive"))
      (node (ref "C13") (pin "+") (pinfunction "+_+") (pintype "passive"))
      (node (ref "C2") (pin "2") (pinfunction "2_2") (pintype "passive"))
      (node (ref "C6") (pin "2") (pinfunction "2_2") (pintype "passive"))
      (node (ref "C9") (pin "1") (pinfunction "1_1") (pintype "passive"))
      (node (ref "J1") (pin "1") (pinfunction "S_1") (pintype "passive"))
      (node (ref "JP1") (pin "2") (pinfunction "2_2") (pintype "passive"))
      (node (ref "L1") (pin "2") (pinfunction "2_2") (pintype "passive"))
      (node (ref "L2") (pin "1") (pinfunction "1_1") (pintype "passive"))
      (node (ref "LDO") (pin "2") (pinfunction "VOUT_2") (pintype "output"))
      (node (ref "LED2") (pin "A") (pinfunction "A_A") (pintype "passive"))
      (node (ref "LM324") (pin "4") (pinfunction "V+_4") (pintype "power_in"))
      (node (ref "R20") (pin "1") (pinfunction "1_1") (pintype "passive"))
      (node (ref "R22") (pin "1") (pinfunction "1_1") (pintype "passive"))
      (node (ref "R27") (pin "1") (pinfunction "1_1") (pintype "passive"))
      (node (ref "R29") (pin "1") (pinfunction "1_1") (pintype "passive"))
      (node (ref "R34") (pin "1") (pinfunction "1_1") (pintype "passive"))
    )
    (net (code "61") (name "unconnected-(AVR-ADC6-Pad19)") (class "Default")
      (node (ref "AVR") (pin "19") (pinfunction "ADC6_19") (pintype "bidirectional"))
    )
    (net (code "62") (name "unconnected-(AVR-ADC7-Pad22)") (class "Default")
      (node (ref "AVR") (pin "22") (pinfunction "ADC7_22") (pintype "bidirectional"))
    )
    (net (code "63") (name "unconnected-(S1-P1-Pad4)") (class "Default")
      (node (ref "S1") (pin "4") (pinfunction "P1_4") (pintype "passive"))
    )
    (net (code "64") (name "unconnected-(S2-P-Pad3)") (class "Default")
      (node (ref "S2") (pin "3") (pinfunction "P_3") (pintype "passive"))
    )
  )
)
